# Clock.net
KiCad netlist of a schematic drawn in Altium Designer
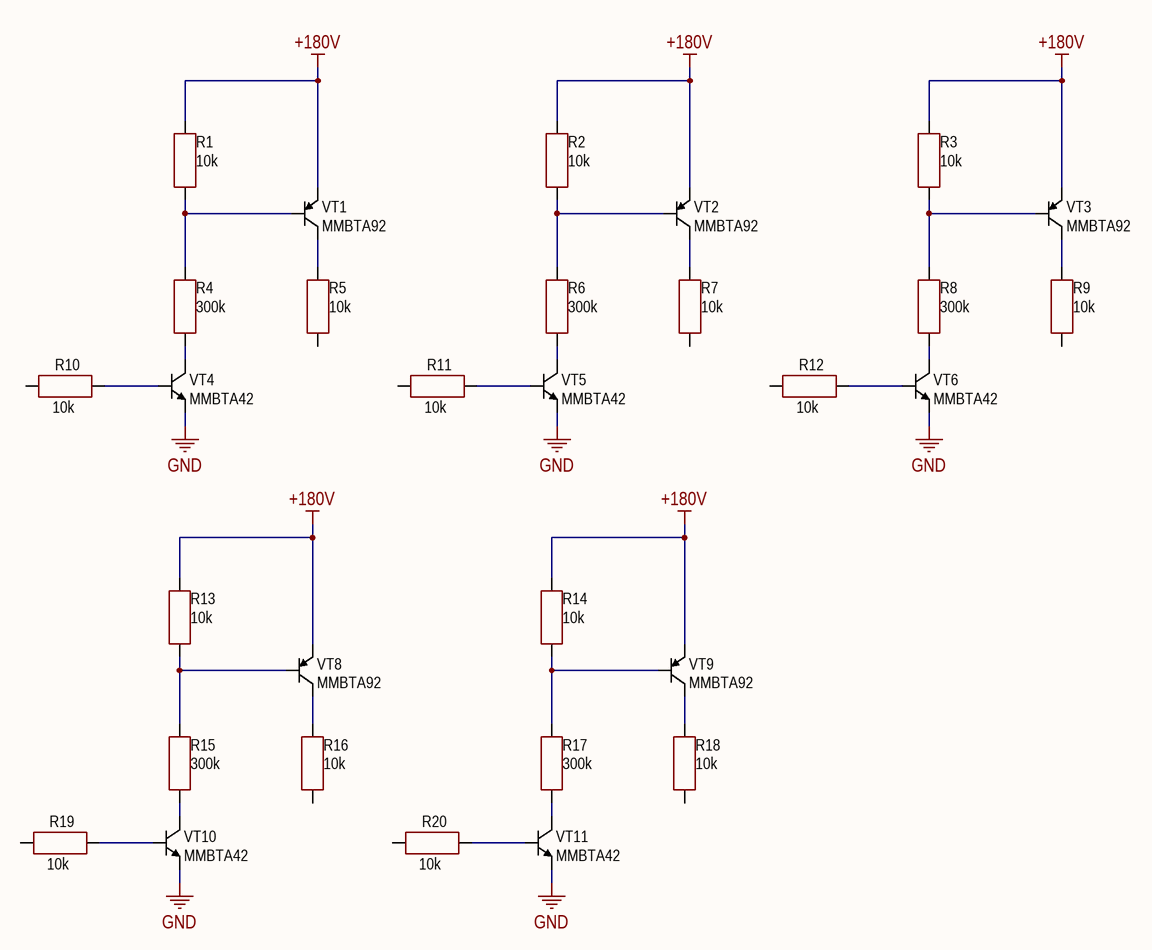
[diagram p0: Clock.SchDoc]

(export (version "E")
  (design (tool "Eeschema 10.0.6"))
  (components
    (comp (ref "R1")
      (value "10k")
      (footprint "RES: 0805")
      (fields
        (field (name "MANUFACTURER") "Yageo")
        (field (name "PARTNUMBER") "RC0805JR-07100RL")
        (field (name "VALUEMANUFACTURERPARTNUMBER") "Resistor film, 10k, ±5%, 0805, 0.125W, -55...+125°C")
      )
      (libsource (lib "") (part "Resistor_0805_1"))
    )
    (comp (ref "R2")
      (value "10k")
      (footprint "RES: 0805")
      (fields
        (field (name "MANUFACTURER") "Yageo")
        (field (name "PARTNUMBER") "RC0805JR-07100RL")
        (field (name "VALUEMANUFACTURERPARTNUMBER") "Resistor film, 10k, ±5%, 0805, 0.125W, -55...+125°C")
      )
      (libsource (lib "resistor") (part "Resistor_0805"))
    )
    (comp (ref "R3")
      (value "10k")
      (footprint "RES: 0805")
      (fields
        (field (name "MANUFACTURER") "Yageo")
        (field (name "PARTNUMBER") "RC0805JR-07100RL")
        (field (name "VALUEMANUFACTURERPARTNUMBER") "Resistor film, 10k, ±5%, 0805, 0.125W, -55...+125°C")
      )
      (libsource (lib "resistor") (part "Resistor_0805"))
    )
    (comp (ref "R4")
      (value "300k")
      (footprint "RES: 0805")
      (fields
        (field (name "MANUFACTURER") "Yageo")
        (field (name "PARTNUMBER") "RC0805JR-07100RL")
        (field (name "VALUEMANUFACTURERPARTNUMBER") "Resistor film, 300k, ±5%, 0805, 0.125W, -55...+125°C")
      )
      (libsource (lib "") (part "Resistor_0805_1"))
    )
    (comp (ref "R5")
      (value "10k")
      (footprint "RES: 0805")
      (fields
        (field (name "MANUFACTURER") "Yageo")
        (field (name "PARTNUMBER") "RC0805JR-07100RL")
        (field (name "VALUEMANUFACTURERPARTNUMBER") "Resistor film, 10k, ±5%, 0805, 0.125W, -55...+125°C")
      )
      (libsource (lib "") (part "Resistor_0805_1"))
    )
    (comp (ref "R6")
      (value "300k")
      (footprint "RES: 0805")
      (fields
        (field (name "MANUFACTURER") "Yageo")
        (field (name "PARTNUMBER") "RC0805JR-07100RL")
        (field (name "VALUEMANUFACTURERPARTNUMBER") "Resistor film, 300k, ±5%, 0805, 0.125W, -55...+125°C")
      )
      (libsource (lib "resistor") (part "Resistor_0805"))
    )
    (comp (ref "R7")
      (value "10k")
      (footprint "RES: 0805")
      (fields
        (field (name "MANUFACTURER") "Yageo")
        (field (name "PARTNUMBER") "RC0805JR-07100RL")
        (field (name "VALUEMANUFACTURERPARTNUMBER") "Resistor film, 10k, ±5%, 0805, 0.125W, -55...+125°C")
      )
      (libsource (lib "resistor") (part "Resistor_0805"))
    )
    (comp (ref "R8")
      (value "300k")
      (footprint "RES: 0805")
      (fields
        (field (name "MANUFACTURER") "Yageo")
        (field (name "PARTNUMBER") "RC0805JR-07100RL")
        (field (name "VALUEMANUFACTURERPARTNUMBER") "Resistor film, 300k, ±5%, 0805, 0.125W, -55...+125°C")
      )
      (libsource (lib "resistor") (part "Resistor_0805"))
    )
    (comp (ref "R9")
      (value "10k")
      (footprint "RES: 0805")
      (fields
        (field (name "MANUFACTURER") "Yageo")
        (field (name "PARTNUMBER") "RC0805JR-07100RL")
        (field (name "VALUEMANUFACTURERPARTNUMBER") "Resistor film, 10k, ±5%, 0805, 0.125W, -55...+125°C")
      )
      (libsource (lib "resistor") (part "Resistor_0805"))
    )
    (comp (ref "R10")
      (value "10k")
      (footprint "RES: 0805")
      (fields
        (field (name "MANUFACTURER") "Yageo")
        (field (name "PARTNUMBER") "RC0805JR-07100RL")
        (field (name "VALUEMANUFACTURERPARTNUMBER") "Resistor film, 10k, ±5%, 0805, 0.125W, -55...+125°C")
      )
      (libsource (lib "") (part "Resistor_0805_2"))
    )
    (comp (ref "R11")
      (value "10k")
      (footprint "RES: 0805")
      (fields
        (field (name "MANUFACTURER") "Yageo")
        (field (name "PARTNUMBER") "RC0805JR-07100RL")
        (field (name "VALUEMANUFACTURERPARTNUMBER") "Resistor film, 10k, ±5%, 0805, 0.125W, -55...+125°C")
      )
      (libsource (lib "") (part "Resistor_0805_2"))
    )
    (comp (ref "R12")
      (value "10k")
      (footprint "RES: 0805")
      (fields
        (field (name "MANUFACTURER") "Yageo")
        (field (name "PARTNUMBER") "RC0805JR-07100RL")
        (field (name "VALUEMANUFACTURERPARTNUMBER") "Resistor film, 10k, ±5%, 0805, 0.125W, -55...+125°C")
      )
      (libsource (lib "") (part "Resistor_0805_3"))
    )
    (comp (ref "R13")
      (value "10k")
      (footprint "RES: 0805")
      (fields
        (field (name "MANUFACTURER") "Yageo")
        (field (name "PARTNUMBER") "RC0805JR-07100RL")
        (field (name "VALUEMANUFACTURERPARTNUMBER") "Resistor film, 10k, ±5%, 0805, 0.125W, -55...+125°C")
      )
      (libsource (lib "resistor") (part "Resistor_0805"))
    )
    (comp (ref "R14")
      (value "10k")
      (footprint "RES: 0805")
      (fields
        (field (name "MANUFACTURER") "Yageo")
        (field (name "PARTNUMBER") "RC0805JR-07100RL")
        (field (name "VALUEMANUFACTURERPARTNUMBER") "Resistor film, 10k, ±5%, 0805, 0.125W, -55...+125°C")
      )
      (libsource (lib "resistor") (part "Resistor_0805"))
    )
    (comp (ref "R15")
      (value "300k")
      (footprint "RES: 0805")
      (fields
        (field (name "MANUFACTURER") "Yageo")
        (field (name "PARTNUMBER") "RC0805JR-07100RL")
        (field (name "VALUEMANUFACTURERPARTNUMBER") "Resistor film, 300k, ±5%, 0805, 0.125W, -55...+125°C")
      )
      (libsource (lib "resistor") (part "Resistor_0805"))
    )
    (comp (ref "R16")
      (value "10k")
      (footprint "RES: 0805")
      (fields
        (field (name "MANUFACTURER") "Yageo")
        (field (name "PARTNUMBER") "RC0805JR-07100RL")
        (field (name "VALUEMANUFACTURERPARTNUMBER") "Resistor film, 10k, ±5%, 0805, 0.125W, -55...+125°C")
      )
      (libsource (lib "resistor") (part "Resistor_0805"))
    )
    (comp (ref "R17")
      (value "300k")
      (footprint "RES: 0805")
      (fields
        (field (name "MANUFACTURER") "Yageo")
        (field (name "PARTNUMBER") "RC0805JR-07100RL")
        (field (name "VALUEMANUFACTURERPARTNUMBER") "Resistor film, 300k, ±5%, 0805, 0.125W, -55...+125°C")
      )
      (libsource (lib "resistor") (part "Resistor_0805"))
    )
    (comp (ref "R18")
      (value "10k")
      (footprint "RES: 0805")
      (fields
        (field (name "MANUFACTURER") "Yageo")
        (field (name "PARTNUMBER") "RC0805JR-07100RL")
        (field (name "VALUEMANUFACTURERPARTNUMBER") "Resistor film, 10k, ±5%, 0805, 0.125W, -55...+125°C")
      )
      (libsource (lib "resistor") (part "Resistor_0805"))
    )
    (comp (ref "R19")
      (value "10k")
      (footprint "RES: 0805")
      (fields
        (field (name "MANUFACTURER") "Yageo")
        (field (name "PARTNUMBER") "RC0805JR-07100RL")
        (field (name "VALUEMANUFACTURERPARTNUMBER") "Resistor film, 10k, ±5%, 0805, 0.125W, -55...+125°C")
      )
      (libsource (lib "") (part "Resistor_0805_4"))
    )
    (comp (ref "R20")
      (value "10k")
      (footprint "RES: 0805")
      (fields
        (field (name "MANUFACTURER") "Yageo")
        (field (name "PARTNUMBER") "RC0805JR-07100RL")
        (field (name "VALUEMANUFACTURERPARTNUMBER") "Resistor film, 10k, ±5%, 0805, 0.125W, -55...+125°C")
      )
      (libsource (lib "") (part "Resistor_0805_4"))
    )
    (comp (ref "VT1")
      (value "~")
      (footprint "SOT23")
      (fields
        (field (name "MANUFACTURER") "ON Semiconductor")
        (field (name "VALUEMANUFACTURERPARTNUMBER") "PNP transistor, 45V, 100mA, 100MHz, 300mW, 0.65V, 220, SOT-23, -55...+125°C")
        (field (name "PARTNUMBER") "MMBTA92")
      )
      (libsource (lib "transistor") (part "BJT_PNP_123"))
    )
    (comp (ref "VT2")
      (value "~")
      (footprint "SOT23")
      (fields
        (field (name "MANUFACTURER") "ON Semiconductor")
        (field (name "VALUEMANUFACTURERPARTNUMBER") "PNP transistor, 45V, 100mA, 100MHz, 300mW, 0.65V, 220, SOT-23, -55...+125°C")
        (field (name "PARTNUMBER") "MMBTA92")
      )
      (libsource (lib "transistor") (part "BJT_PNP_123"))
    )
    (comp (ref "VT3")
      (value "~")
      (footprint "SOT23")
      (fields
        (field (name "MANUFACTURER") "ON Semiconductor")
        (field (name "VALUEMANUFACTURERPARTNUMBER") "PNP transistor, 45V, 100mA, 100MHz, 300mW, 0.65V, 220, SOT-23, -55...+125°C")
        (field (name "PARTNUMBER") "MMBTA92")
      )
      (libsource (lib "transistor") (part "BJT_PNP_123"))
    )
    (comp (ref "VT4")
      (value "~")
      (footprint "SOT23")
      (fields
        (field (name "MANUFACTURER") "ON Semiconductor")
        (field (name "VALUEMANUFACTURERPARTNUMBER") "NPN transistor, 45V, 100mA, 100MHz, 300mW, 0.6V, 420, SOT-23, -55...+125°C")
        (field (name "PARTNUMBER") "MMBTA42")
      )
      (libsource (lib "transistor") (part "BJT_NPN_132"))
    )
    (comp (ref "VT5")
      (value "~")
      (footprint "SOT23")
      (fields
        (field (name "MANUFACTURER") "ON Semiconductor")
        (field (name "VALUEMANUFACTURERPARTNUMBER") "NPN transistor, 45V, 100mA, 100MHz, 300mW, 0.6V, 420, SOT-23, -55...+125°C")
        (field (name "PARTNUMBER") "MMBTA42")
      )
      (libsource (lib "transistor") (part "BJT_NPN_132"))
    )
    (comp (ref "VT6")
      (value "~")
      (footprint "SOT23")
      (fields
        (field (name "MANUFACTURER") "ON Semiconductor")
        (field (name "VALUEMANUFACTURERPARTNUMBER") "NPN transistor, 45V, 100mA, 100MHz, 300mW, 0.6V, 420, SOT-23, -55...+125°C")
        (field (name "PARTNUMBER") "MMBTA42")
      )
      (libsource (lib "transistor") (part "BJT_NPN_132"))
    )
    (comp (ref "VT8")
      (value "~")
      (footprint "SOT23")
      (fields
        (field (name "MANUFACTURER") "ON Semiconductor")
        (field (name "VALUEMANUFACTURERPARTNUMBER") "PNP transistor, 45V, 100mA, 100MHz, 300mW, 0.65V, 220, SOT-23, -55...+125°C")
        (field (name "PARTNUMBER") "MMBTA92")
      )
      (libsource (lib "transistor") (part "BJT_PNP_123"))
    )
    (comp (ref "VT9")
      (value "~")
      (footprint "SOT23")
      (fields
        (field (name "MANUFACTURER") "ON Semiconductor")
        (field (name "VALUEMANUFACTURERPARTNUMBER") "PNP transistor, 45V, 100mA, 100MHz, 300mW, 0.65V, 220, SOT-23, -55...+125°C")
        (field (name "PARTNUMBER") "MMBTA92")
      )
      (libsource (lib "transistor") (part "BJT_PNP_123"))
    )
    (comp (ref "VT10")
      (value "~")
      (footprint "SOT23")
      (fields
        (field (name "MANUFACTURER") "ON Semiconductor")
        (field (name "VALUEMANUFACTURERPARTNUMBER") "NPN transistor, 45V, 100mA, 100MHz, 300mW, 0.6V, 420, SOT-23, -55...+125°C")
        (field (name "PARTNUMBER") "MMBTA42")
      )
      (libsource (lib "transistor") (part "BJT_NPN_132"))
    )
    (comp (ref "VT11")
      (value "~")
      (footprint "SOT23")
      (fields
        (field (name "MANUFACTURER") "ON Semiconductor")
        (field (name "VALUEMANUFACTURERPARTNUMBER") "NPN transistor, 45V, 100mA, 100MHz, 300mW, 0.6V, 420, SOT-23, -55...+125°C")
        (field (name "PARTNUMBER") "MMBTA42")
      )
      (libsource (lib "transistor") (part "BJT_NPN_132"))
    )
  )
  (nets
    (net (code "1") (name "+180V") (class "Default")
      (node (ref "R1") (pin "2") (pinfunction "2_2") (pintype "passive"))
      (node (ref "R13") (pin "2") (pinfunction "2_2") (pintype "passive"))
      (node (ref "R14") (pin "2") (pinfunction "2_2") (pintype "passive"))
      (node (ref "R2") (pin "2") (pinfunction "2_2") (pintype "passive"))
      (node (ref "R3") (pin "2") (pinfunction "2_2") (pintype "passive"))
      (node (ref "VT1") (pin "2") (pinfunction "E_2") (pintype "passive"))
      (node (ref "VT2") (pin "2") (pinfunction "E_2") (pintype "passive"))
      (node (ref "VT3") (pin "2") (pinfunction "E_2") (pintype "passive"))
      (node (ref "VT8") (pin "2") (pinfunction "E_2") (pintype "passive"))
      (node (ref "VT9") (pin "2") (pinfunction "E_2") (pintype "passive"))
    )
    (net (code "2") (name "GND") (class "Default")
      (node (ref "VT10") (pin "2") (pinfunction "E_2") (pintype "passive"))
      (node (ref "VT11") (pin "2") (pinfunction "E_2") (pintype "passive"))
      (node (ref "VT4") (pin "2") (pinfunction "E_2") (pintype "passive"))
      (node (ref "VT5") (pin "2") (pinfunction "E_2") (pintype "passive"))
      (node (ref "VT6") (pin "2") (pinfunction "E_2") (pintype "passive"))
    )
    (net (code "3") (name "Net-(VT1-B)") (class "Default")
      (node (ref "R1") (pin "1") (pinfunction "1_1") (pintype "passive"))
      (node (ref "R4") (pin "2") (pinfunction "2_2") (pintype "passive"))
      (node (ref "VT1") (pin "1") (pinfunction "B_1") (pintype "passive"))
    )
    (net (code "4") (name "Net-(VT1-C)") (class "Default")
      (node (ref "R5") (pin "2") (pinfunction "2_2") (pintype "passive"))
      (node (ref "VT1") (pin "3") (pinfunction "C_3") (pintype "passive"))
    )
    (net (code "5") (name "Net-(VT2-B)") (class "Default")
      (node (ref "R2") (pin "1") (pinfunction "1_1") (pintype "passive"))
      (node (ref "R6") (pin "2") (pinfunction "2_2") (pintype "passive"))
      (node (ref "VT2") (pin "1") (pinfunction "B_1") (pintype "passive"))
    )
    (net (code "6") (name "Net-(VT2-C)") (class "Default")
      (node (ref "R7") (pin "2") (pinfunction "2_2") (pintype "passive"))
      (node (ref "VT2") (pin "3") (pinfunction "C_3") (pintype "passive"))
    )
    (net (code "7") (name "Net-(VT3-B)") (class "Default")
      (node (ref "R3") (pin "1") (pinfunction "1_1") (pintype "passive"))
      (node (ref "R8") (pin "2") (pinfunction "2_2") (pintype "passive"))
      (node (ref "VT3") (pin "1") (pinfunction "B_1") (pintype "passive"))
    )
    (net (code "8") (name "Net-(VT3-C)") (class "Default")
      (node (ref "R9") (pin "2") (pinfunction "2_2") (pintype "passive"))
      (node (ref "VT3") (pin "3") (pinfunction "C_3") (pintype "passive"))
    )
    (net (code "9") (name "Net-(VT4-B)") (class "Default")
      (node (ref "R10") (pin "2") (pinfunction "2_2") (pintype "passive"))
      (node (ref "VT4") (pin "1") (pinfunction "B_1") (pintype "passive"))
    )
    (net (code "10") (name "Net-(VT4-C)") (class "Default")
      (node (ref "R4") (pin "1") (pinfunction "1_1") (pintype "passive"))
      (node (ref "VT4") (pin "3") (pinfunction "C_3") (pintype "passive"))
    )
    (net (code "11") (name "Net-(VT5-B)") (class "Default")
      (node (ref "R11") (pin "2") (pinfunction "2_2") (pintype "passive"))
      (node (ref "VT5") (pin "1") (pinfunction "B_1") (pintype "passive"))
    )
    (net (code "12") (name "Net-(VT5-C)") (class "Default")
      (node (ref "R6") (pin "1") (pinfunction "1_1") (pintype "passive"))
      (node (ref "VT5") (pin "3") (pinfunction "C_3") (pintype "passive"))
    )
    (net (code "13") (name "Net-(VT6-B)") (class "Default")
      (node (ref "R12") (pin "2") (pinfunction "2_2") (pintype "passive"))
      (node (ref "VT6") (pin "1") (pinfunction "B_1") (pintype "passive"))
    )
    (net (code "14") (name "Net-(VT6-C)") (class "Default")
      (node (ref "R8") (pin "1") (pinfunction "1_1") (pintype "passive"))
      (node (ref "VT6") (pin "3") (pinfunction "C_3") (pintype "passive"))
    )
    (net (code "15") (name "Net-(VT8-B)") (class "Default")
      (node (ref "R13") (pin "1") (pinfunction "1_1") (pintype "passive"))
      (node (ref "R15") (pin "2") (pinfunction "2_2") (pintype "passive"))
      (node (ref "VT8") (pin "1") (pinfunction "B_1") (pintype "passive"))
    )
    (net (code "16") (name "Net-(VT8-C)") (class "Default")
      (node (ref "R16") (pin "2") (pinfunction "2_2") (pintype "passive"))
      (node (ref "VT8") (pin "3") (pinfunction "C_3") (pintype "passive"))
    )
    (net (code "17") (name "Net-(VT9-B)") (class "Default")
      (node (ref "R14") (pin "1") (pinfunction "1_1") (pintype "passive"))
      (node (ref "R17") (pin "2") (pinfunction "2_2") (pintype "passive"))
      (node (ref "VT9") (pin "1") (pinfunction "B_1") (pintype "passive"))
    )
    (net (code "18") (name "Net-(VT9-C)") (class "Default")
      (node (ref "R18") (pin "2") (pinfunction "2_2") (pintype "passive"))
      (node (ref "VT9") (pin "3") (pinfunction "C_3") (pintype "passive"))
    )
    (net (code "19") (name "Net-(VT10-B)") (class "Default")
      (node (ref "R19") (pin "2") (pinfunction "2_2") (pintype "passive"))
      (node (ref "VT10") (pin "1") (pinfunction "B_1") (pintype "passive"))
    )
    (net (code "20") (name "Net-(VT10-C)") (class "Default")
      (node (ref "R15") (pin "1") (pinfunction "1_1") (pintype "passive"))
      (node (ref "VT10") (pin "3") (pinfunction "C_3") (pintype "passive"))
    )
    (net (code "21") (name "Net-(VT11-B)") (class "Default")
      (node (ref "R20") (pin "2") (pinfunction "2_2") (pintype "passive"))
      (node (ref "VT11") (pin "1") (pinfunction "B_1") (pintype "passive"))
    )
    (net (code "22") (name "Net-(VT11-C)") (class "Default")
      (node (ref "R17") (pin "1") (pinfunction "1_1") (pintype "passive"))
      (node (ref "VT11") (pin "3") (pinfunction "C_3") (pintype "passive"))
    )
    (net (code "23") (name "unconnected-(R5-Pad1)") (class "Default")
      (node (ref "R5") (pin "1") (pinfunction "1_1") (pintype "passive"))
    )
    (net (code "24") (name "unconnected-(R7-Pad1)") (class "Default")
      (node (ref "R7") (pin "1") (pinfunction "1_1") (pintype "passive"))
    )
    (net (code "25") (name "unconnected-(R9-Pad1)") (class "Default")
      (node (ref "R9") (pin "1") (pinfunction "1_1") (pintype "passive"))
    )
    (net (code "26") (name "unconnected-(R10-Pad1)") (class "Default")
      (node (ref "R10") (pin "1") (pinfunction "1_1") (pintype "passive"))
    )
    (net (code "27") (name "unconnected-(R11-Pad1)") (class "Default")
      (node (ref "R11") (pin "1") (pinfunction "1_1") (pintype "passive"))
    )
    (net (code "28") (name "unconnected-(R12-Pad1)") (class "Default")
      (node (ref "R12") (pin "1") (pinfunction "1_1") (pintype "passive"))
    )
    (net (code "29") (name "unconnected-(R16-Pad1)") (class "Default")
      (node (ref "R16") (pin "1") (pinfunction "1_1") (pintype "passive"))
    )
    (net (code "30") (name "unconnected-(R18-Pad1)") (class "Default")
      (node (ref "R18") (pin "1") (pinfunction "1_1") (pintype "passive"))
    )
    (net (code "31") (name "unconnected-(R19-Pad1)") (class "Default")
      (node (ref "R19") (pin "1") (pinfunction "1_1") (pintype "passive"))
    )
    (net (code "32") (name "unconnected-(R20-Pad1)") (class "Default")
      (node (ref "R20") (pin "1") (pinfunction "1_1") (pintype "passive"))
    )
  )
)
